# IMU.net
KiCad netlist of a schematic drawn in Altium Designer
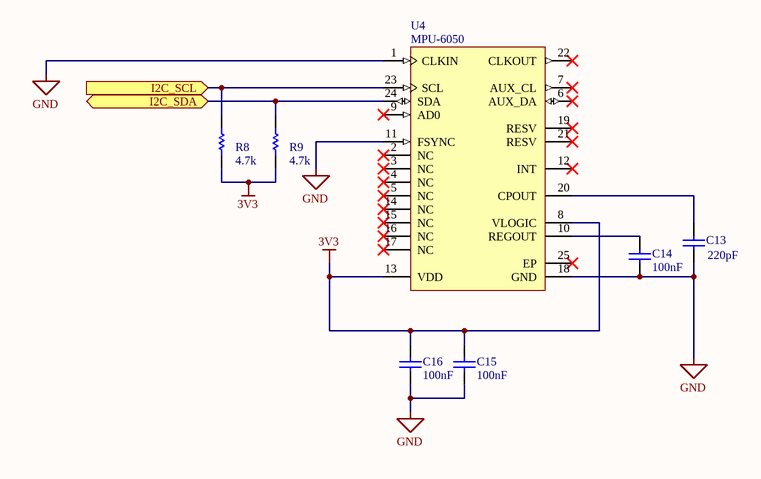
[diagram p0: IMU.SchDoc]

(export (version "E")
  (design (tool "Eeschema 10.0.6"))
  (components
    (comp (ref "C13")
      (value "220pF")
      (footprint "CAPC2013X88X50ML20T25")
      (fields (field (name "PART NUMBER") "C0805C221J5GACTU") (field (name "MANUFACTURER") "Kemet"))
      (libsource (lib "Altium Content Vault") (part "CAP"))
    )
    (comp (ref "C14")
      (value "100nF")
      (footprint "CAPC2013X94X50ML20T25")
      (fields
        (field (name "MANUFACTURER") "AVX Interconnect / Elco")
        (field (name "PART NUMBER") "08051C152KAT2A")
      )
      (libsource (lib "Altium Content Vault") (part "CAP"))
    )
    (comp (ref "C15")
      (value "100nF")
      (footprint "CAPC2013X94X50ML20T25")
      (fields
        (field (name "MANUFACTURER") "AVX Interconnect / Elco")
        (field (name "PART NUMBER") "08051C152KAT2A")
      )
      (libsource (lib "Altium Content Vault") (part "CAP"))
    )
    (comp (ref "C16")
      (value "100nF")
      (footprint "CAPC2013X94X50ML20T25")
      (fields
        (field (name "MANUFACTURER") "AVX Interconnect / Elco")
        (field (name "PART NUMBER") "08051C152KAT2A")
      )
      (libsource (lib "Altium Content Vault") (part "CAP"))
    )
    (comp (ref "R8")
      (value "4.7k")
      (footprint "RESC2013X60X40ML20T25")
      (fields (field (name "PART NUMBER") "ERA6AEB472V") (field (name "MANUFACTURER") "Panasonic"))
      (libsource (lib "Altium Content Vault") (part "RES"))
    )
    (comp (ref "R9")
      (value "4.7k")
      (footprint "RESC2013X60X40ML20T25")
      (fields (field (name "PART NUMBER") "ERA6AEB472V") (field (name "MANUFACTURER") "Panasonic"))
      (libsource (lib "Altium Content Vault") (part "RES"))
    )
    (comp (ref "U4")
      (value "MPU-6050")
      (footprint "IS-QFN-24_V")
      (fields (field (name "MANUFACTURER") "InvenSense"))
      (libsource (lib "Altium Content Vault") (part "IS-MPU-6050-QFN-24"))
    )
  )
  (nets
    (net (code "1") (name "/I2C_SCL") (class "Default")
      (node (ref "R8") (pin "2") (pinfunction "2_2") (pintype "passive"))
      (node (ref "U4") (pin "23") (pinfunction "SCL_23") (pintype "input"))
    )
    (net (code "2") (name "/I2C_SDA") (class "Default")
      (node (ref "R9") (pin "2") (pinfunction "2_2") (pintype "passive"))
      (node (ref "U4") (pin "24") (pinfunction "SDA_24") (pintype "bidirectional"))
    )
    (net (code "3") (name "3V3") (class "Default")
      (node (ref "C15") (pin "2") (pinfunction "2_2") (pintype "passive"))
      (node (ref "C16") (pin "2") (pinfunction "2_2") (pintype "passive"))
      (node (ref "R8") (pin "1") (pinfunction "1_1") (pintype "passive"))
      (node (ref "R9") (pin "1") (pinfunction "1_1") (pintype "passive"))
      (node (ref "U4") (pin "13") (pinfunction "VDD_13") (pintype "passive"))
      (node (ref "U4") (pin "8") (pinfunction "VLOGIC_8") (pintype "passive"))
    )
    (net (code "4") (name "GND") (class "Default")
      (node (ref "C13") (pin "1") (pinfunction "1_1") (pintype "passive"))
      (node (ref "C14") (pin "1") (pinfunction "1_1") (pintype "passive"))
      (node (ref "C15") (pin "1") (pinfunction "1_1") (pintype "passive"))
      (node (ref "C16") (pin "1") (pinfunction "1_1") (pintype "passive"))
      (node (ref "U4") (pin "1") (pinfunction "CLKIN_1") (pintype "input"))
      (node (ref "U4") (pin "11") (pinfunction "FSYNC_11") (pintype "input"))
      (node (ref "U4") (pin "18") (pinfunction "GND_18") (pintype "passive"))
    )
    (net (code "5") (name "Net-(U4-CPOUT)") (class "Default")
      (node (ref "C13") (pin "2") (pinfunction "2_2") (pintype "passive"))
      (node (ref "U4") (pin "20") (pinfunction "CPOUT_20") (pintype "passive"))
    )
    (net (code "6") (name "Net-(U4-REGOUT)") (class "Default")
      (node (ref "C14") (pin "2") (pinfunction "2_2") (pintype "passive"))
      (node (ref "U4") (pin "10") (pinfunction "REGOUT_10") (pintype "passive"))
    )
    (net (code "7") (name "unconnected-(U4-AD0-Pad9)") (class "Default")
      (node (ref "U4") (pin "9") (pinfunction "AD0_9") (pintype "input+no_connect"))
    )
    (net (code "8") (name "unconnected-(U4-AUX_CL-Pad7)") (class "Default")
      (node (ref "U4") (pin "7") (pinfunction "AUX_CL_7") (pintype "output+no_connect"))
    )
    (net (code "9") (name "unconnected-(U4-AUX_DA-Pad6)") (class "Default")
      (node (ref "U4") (pin "6") (pinfunction "AUX_DA_6") (pintype "bidirectional+no_connect"))
    )
    (net (code "10") (name "unconnected-(U4-CLKOUT-Pad22)") (class "Default")
      (node (ref "U4") (pin "22") (pinfunction "CLKOUT_22") (pintype "output+no_connect"))
    )
    (net (code "11") (name "unconnected-(U4-EP-Pad25)") (class "Default")
      (node (ref "U4") (pin "25") (pinfunction "EP_25") (pintype "power_in+no_connect"))
    )
    (net (code "12") (name "unconnected-(U4-INT-Pad12)") (class "Default")
      (node (ref "U4") (pin "12") (pinfunction "INT_12") (pintype "open_collector+no_connect"))
    )
    (net (code "13") (name "unconnected-(U4-NC-Pad2)") (class "Default")
      (node (ref "U4") (pin "2") (pinfunction "NC_2") (pintype "passive+no_connect"))
    )
    (net (code "14") (name "unconnected-(U4-NC-Pad3)") (class "Default")
      (node (ref "U4") (pin "3") (pinfunction "NC_3") (pintype "passive+no_connect"))
    )
    (net (code "15") (name "unconnected-(U4-NC-Pad4)") (class "Default")
      (node (ref "U4") (pin "4") (pinfunction "NC_4") (pintype "passive+no_connect"))
    )
    (net (code "16") (name "unconnected-(U4-NC-Pad5)") (class "Default")
      (node (ref "U4") (pin "5") (pinfunction "NC_5") (pintype "passive+no_connect"))
    )
    (net (code "17") (name "unconnected-(U4-NC-Pad14)") (class "Default")
      (node (ref "U4") (pin "14") (pinfunction "NC_14") (pintype "passive+no_connect"))
    )
    (net (code "18") (name "unconnected-(U4-NC-Pad15)") (class "Default")
      (node (ref "U4") (pin "15") (pinfunction "NC_15") (pintype "passive+no_connect"))
    )
    (net (code "19") (name "unconnected-(U4-NC-Pad16)") (class "Default")
      (node (ref "U4") (pin "16") (pinfunction "NC_16") (pintype "passive+no_connect"))
    )
    (net (code "20") (name "unconnected-(U4-NC-Pad17)") (class "Default")
      (node (ref "U4") (pin "17") (pinfunction "NC_17") (pintype "passive+no_connect"))
    )
    (net (code "21") (name "unconnected-(U4-RESV-Pad19)") (class "Default")
      (node (ref "U4") (pin "19") (pinfunction "RESV_19") (pintype "passive+no_connect"))
    )
    (net (code "22") (name "unconnected-(U4-RESV-Pad21)") (class "Default")
      (node (ref "U4") (pin "21") (pinfunction "RESV_21") (pintype "passive+no_connect"))
    )
  )
)
